# chess.net
KiCad netlist of a schematic drawn in EAGLE
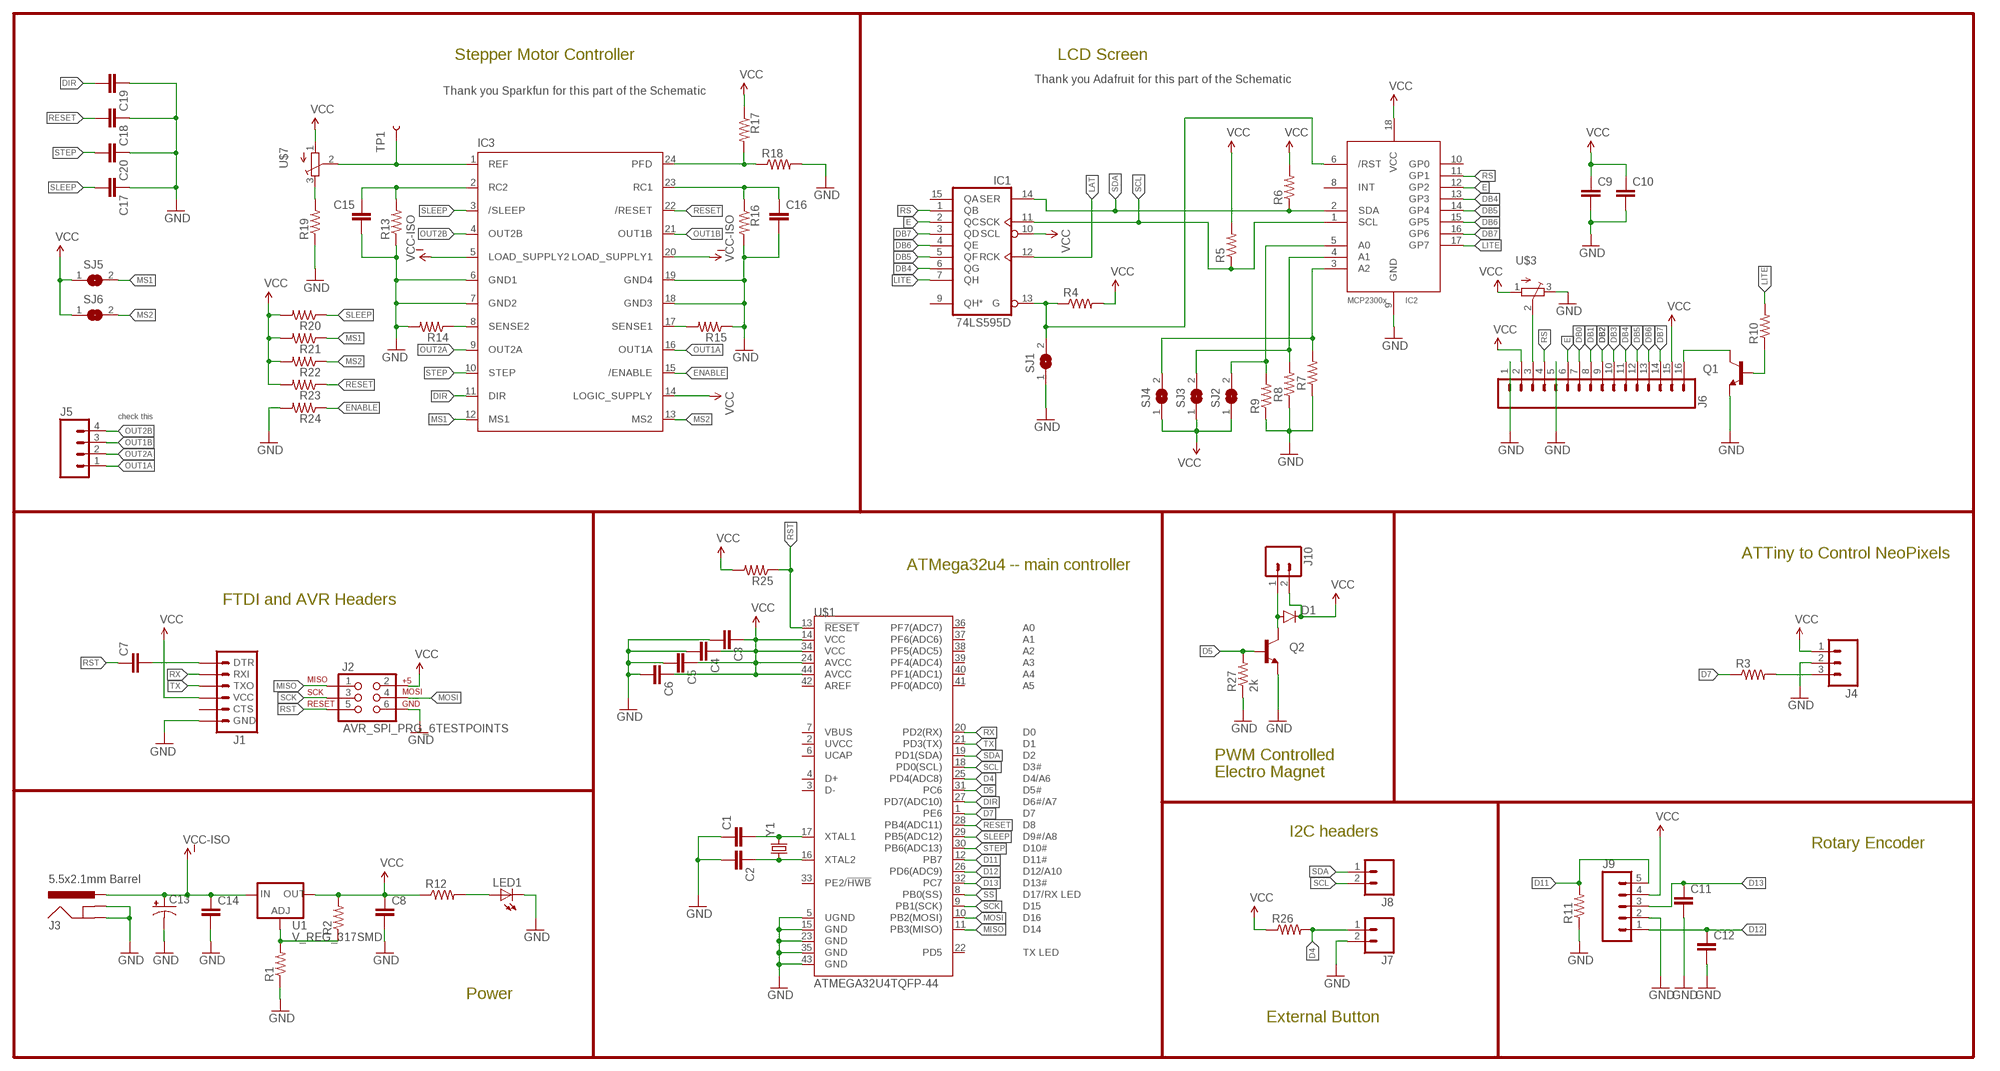
[diagram p0: schematic, sheet 1]

(export (version "E")
  (design (tool "Eeschema 10.0.6"))
  (components
    (comp (ref "C1")
      (value "CAP0603-CAP")
      (footprint "eagle-import:0603-CAP")
      (libsource (lib "eagle-import") (part "CAP0603-CAP"))
    )
    (comp (ref "C2")
      (value "CAP0603-CAP")
      (footprint "eagle-import:0603-CAP")
      (libsource (lib "eagle-import") (part "CAP0603-CAP"))
    )
    (comp (ref "C3")
      (value "CAP0603-CAP")
      (footprint "eagle-import:0603-CAP")
      (libsource (lib "eagle-import") (part "CAP0603-CAP"))
    )
    (comp (ref "C4")
      (value "CAP0603-CAP")
      (footprint "eagle-import:0603-CAP")
      (libsource (lib "eagle-import") (part "CAP0603-CAP"))
    )
    (comp (ref "C5")
      (value "CAP0603-CAP")
      (footprint "eagle-import:0603-CAP")
      (libsource (lib "eagle-import") (part "CAP0603-CAP"))
    )
    (comp (ref "C6")
      (value "CAP0603-CAP")
      (footprint "eagle-import:0603-CAP")
      (libsource (lib "eagle-import") (part "CAP0603-CAP"))
    )
    (comp (ref "C7")
      (value "CAP0603-CAP")
      (footprint "eagle-import:0603-CAP")
      (libsource (lib "eagle-import") (part "CAP0603-CAP"))
    )
    (comp (ref "C8")
      (value "CAP0603-CAP")
      (footprint "eagle-import:0603-CAP")
      (libsource (lib "eagle-import") (part "CAP0603-CAP"))
    )
    (comp (ref "C9")
      (value "CAP0603-CAP")
      (footprint "eagle-import:0603-CAP")
      (libsource (lib "eagle-import") (part "CAP0603-CAP"))
    )
    (comp (ref "C10")
      (value "CAP0603-CAP")
      (footprint "eagle-import:0603-CAP")
      (libsource (lib "eagle-import") (part "CAP0603-CAP"))
    )
    (comp (ref "C11")
      (value "CAP0603-CAP")
      (footprint "eagle-import:0603-CAP")
      (libsource (lib "eagle-import") (part "CAP0603-CAP"))
    )
    (comp (ref "C12")
      (value "CAP0603-CAP")
      (footprint "eagle-import:0603-CAP")
      (libsource (lib "eagle-import") (part "CAP0603-CAP"))
    )
    (comp (ref "C13")
      (value "CAP_POL6032")
      (footprint "eagle-import:EIA6032")
      (libsource (lib "eagle-import") (part "CAP_POL6032"))
    )
    (comp (ref "C14")
      (value "CAP0603-CAP")
      (footprint "eagle-import:0603-CAP")
      (libsource (lib "eagle-import") (part "CAP0603-CAP"))
    )
    (comp (ref "C15")
      (value "CAP0603-CAP")
      (footprint "eagle-import:0603-CAP")
      (libsource (lib "eagle-import") (part "CAP0603-CAP"))
    )
    (comp (ref "C16")
      (value "CAP0603-CAP")
      (footprint "eagle-import:0603-CAP")
      (libsource (lib "eagle-import") (part "CAP0603-CAP"))
    )
    (comp (ref "C17")
      (value "CAP0603-CAP")
      (footprint "eagle-import:0603-CAP")
      (libsource (lib "eagle-import") (part "CAP0603-CAP"))
    )
    (comp (ref "C18")
      (value "CAP0603-CAP")
      (footprint "eagle-import:0603-CAP")
      (libsource (lib "eagle-import") (part "CAP0603-CAP"))
    )
    (comp (ref "C19")
      (value "CAP0603-CAP")
      (footprint "eagle-import:0603-CAP")
      (libsource (lib "eagle-import") (part "CAP0603-CAP"))
    )
    (comp (ref "C20")
      (value "CAP0603-CAP")
      (footprint "eagle-import:0603-CAP")
      (libsource (lib "eagle-import") (part "CAP0603-CAP"))
    )
    (comp (ref "D1")
      (value "DIODEBAS16")
      (footprint "eagle-import:SOD-323")
      (libsource (lib "eagle-import") (part "DIODEBAS16"))
    )
    (comp (ref "IC1")
      (value "74LS595D")
      (footprint "eagle-import:SO16")
      (libsource (lib "eagle-import") (part "74595DLS"))
    )
    (comp (ref "IC2")
      (value "MCP2300X/SO")
      (footprint "eagle-import:SO18W")
      (libsource (lib "eagle-import") (part "MCP2300X/SO"))
    )
    (comp (ref "IC3")
      (value "A3967SLB")
      (footprint "eagle-import:SO24W")
      (libsource (lib "eagle-import") (part "A3967SLB"))
    )
    (comp (ref "J1")
      (value "ARDUINO_SERIAL_PROGRAMPTH")
      (footprint "eagle-import:1X06")
      (libsource (lib "eagle-import") (part "ARDUINO_SERIAL_PROGRAMPTH"))
    )
    (comp (ref "J2")
      (value "AVR_SPI_PRG_6TESTPOINTS")
      (footprint "eagle-import:2X3_TEST_POINTS")
      (libsource (lib "eagle-import") (part "AVR_SPI_PRG_6TESTPOINTS"))
    )
    (comp (ref "J3")
      (value "5.5x2.1mm Barrel")
      (footprint "eagle-import:POWER_JACK_SMD")
      (libsource (lib "eagle-import") (part "POWER_JACKSMD"))
    )
    (comp (ref "J4")
      (value "M03PTH")
      (footprint "eagle-import:1X03")
      (libsource (lib "eagle-import") (part "M03PTH"))
    )
    (comp (ref "J5")
      (value "M04PTH")
      (footprint "eagle-import:1X04")
      (libsource (lib "eagle-import") (part "M04PTH"))
    )
    (comp (ref "J6")
      (value "M16PTH")
      (footprint "eagle-import:1X16")
      (libsource (lib "eagle-import") (part "M16PTH"))
    )
    (comp (ref "J7")
      (value "M02PTH")
      (footprint "eagle-import:1X02")
      (libsource (lib "eagle-import") (part "M02PTH"))
    )
    (comp (ref "J8")
      (value "M02PTH")
      (footprint "eagle-import:1X02")
      (libsource (lib "eagle-import") (part "M02PTH"))
    )
    (comp (ref "J9")
      (value "M05PTH")
      (footprint "eagle-import:1X05")
      (libsource (lib "eagle-import") (part "M05PTH"))
    )
    (comp (ref "J10")
      (value "M02PTH")
      (footprint "eagle-import:1X02")
      (libsource (lib "eagle-import") (part "M02PTH"))
    )
    (comp (ref "LED1")
      (value "LED1206")
      (footprint "eagle-import:LED-1206")
      (libsource (lib "eagle-import") (part "LED1206"))
    )
    (comp (ref "Q1")
      (value "TRANSISTOR_NPNMMBT2222A")
      (footprint "eagle-import:SOT23-3")
      (libsource (lib "eagle-import") (part "TRANSISTOR_NPNMMBT2222A"))
    )
    (comp (ref "Q2")
      (value "TRANSISTOR_NPNTO-92-AMMO")
      (footprint "eagle-import:TO-92-AMMO")
      (libsource (lib "eagle-import") (part "TRANSISTOR_NPNTO-92-AMMO"))
    )
    (comp (ref "R1")
      (value "RESISTOR0603-RES")
      (footprint "eagle-import:0603-RES")
      (libsource (lib "eagle-import") (part "RESISTOR0603-RES"))
    )
    (comp (ref "R2")
      (value "RESISTOR0603-RES")
      (footprint "eagle-import:0603-RES")
      (libsource (lib "eagle-import") (part "RESISTOR0603-RES"))
    )
    (comp (ref "R3")
      (value "RESISTOR0603-RES")
      (footprint "eagle-import:0603-RES")
      (libsource (lib "eagle-import") (part "RESISTOR0603-RES"))
    )
    (comp (ref "R4")
      (value "RESISTOR0603-RES")
      (footprint "eagle-import:0603-RES")
      (libsource (lib "eagle-import") (part "RESISTOR0603-RES"))
    )
    (comp (ref "R5")
      (value "RESISTOR0603-RES")
      (footprint "eagle-import:0603-RES")
      (libsource (lib "eagle-import") (part "RESISTOR0603-RES"))
    )
    (comp (ref "R6")
      (value "RESISTOR0603-RES")
      (footprint "eagle-import:0603-RES")
      (libsource (lib "eagle-import") (part "RESISTOR0603-RES"))
    )
    (comp (ref "R7")
      (value "RESISTOR0603-RES")
      (footprint "eagle-import:0603-RES")
      (libsource (lib "eagle-import") (part "RESISTOR0603-RES"))
    )
    (comp (ref "R8")
      (value "RESISTOR0603-RES")
      (footprint "eagle-import:0603-RES")
      (libsource (lib "eagle-import") (part "RESISTOR0603-RES"))
    )
    (comp (ref "R9")
      (value "RESISTOR0603-RES")
      (footprint "eagle-import:0603-RES")
      (libsource (lib "eagle-import") (part "RESISTOR0603-RES"))
    )
    (comp (ref "R10")
      (value "RESISTOR0603-RES")
      (footprint "eagle-import:0603-RES")
      (libsource (lib "eagle-import") (part "RESISTOR0603-RES"))
    )
    (comp (ref "R11")
      (value "RESISTOR0603-RES")
      (footprint "eagle-import:0603-RES")
      (libsource (lib "eagle-import") (part "RESISTOR0603-RES"))
    )
    (comp (ref "R12")
      (value "RESISTOR0603-RES")
      (footprint "eagle-import:0603-RES")
      (libsource (lib "eagle-import") (part "RESISTOR0603-RES"))
    )
    (comp (ref "R13")
      (value "RESISTOR0603-RES")
      (footprint "eagle-import:0603-RES")
      (libsource (lib "eagle-import") (part "RESISTOR0603-RES"))
    )
    (comp (ref "R14")
      (value "RESISTOR0603-RES")
      (footprint "eagle-import:0603-RES")
      (libsource (lib "eagle-import") (part "RESISTOR0603-RES"))
    )
    (comp (ref "R15")
      (value "RESISTOR0603-RES")
      (footprint "eagle-import:0603-RES")
      (libsource (lib "eagle-import") (part "RESISTOR0603-RES"))
    )
    (comp (ref "R16")
      (value "RESISTOR0603-RES")
      (footprint "eagle-import:0603-RES")
      (libsource (lib "eagle-import") (part "RESISTOR0603-RES"))
    )
    (comp (ref "R17")
      (value "RESISTOR0603-RES")
      (footprint "eagle-import:0603-RES")
      (libsource (lib "eagle-import") (part "RESISTOR0603-RES"))
    )
    (comp (ref "R18")
      (value "RESISTOR0603-RES")
      (footprint "eagle-import:0603-RES")
      (libsource (lib "eagle-import") (part "RESISTOR0603-RES"))
    )
    (comp (ref "R19")
      (value "RESISTOR0603-RES")
      (footprint "eagle-import:0603-RES")
      (libsource (lib "eagle-import") (part "RESISTOR0603-RES"))
    )
    (comp (ref "R20")
      (value "RESISTOR0603-RES")
      (footprint "eagle-import:0603-RES")
      (libsource (lib "eagle-import") (part "RESISTOR0603-RES"))
    )
    (comp (ref "R21")
      (value "RESISTOR0603-RES")
      (footprint "eagle-import:0603-RES")
      (libsource (lib "eagle-import") (part "RESISTOR0603-RES"))
    )
    (comp (ref "R22")
      (value "RESISTOR0603-RES")
      (footprint "eagle-import:0603-RES")
      (libsource (lib "eagle-import") (part "RESISTOR0603-RES"))
    )
    (comp (ref "R23")
      (value "RESISTOR0603-RES")
      (footprint "eagle-import:0603-RES")
      (libsource (lib "eagle-import") (part "RESISTOR0603-RES"))
    )
    (comp (ref "R24")
      (value "RESISTOR0603-RES")
      (footprint "eagle-import:0603-RES")
      (libsource (lib "eagle-import") (part "RESISTOR0603-RES"))
    )
    (comp (ref "R25")
      (value "RESISTOR0603-RES")
      (footprint "eagle-import:0603-RES")
      (libsource (lib "eagle-import") (part "RESISTOR0603-RES"))
    )
    (comp (ref "R26")
      (value "RESISTOR0603-RES")
      (footprint "eagle-import:0603-RES")
      (libsource (lib "eagle-import") (part "RESISTOR0603-RES"))
    )
    (comp (ref "R27")
      (value "2k")
      (footprint "eagle-import:0603-RES")
      (libsource (lib "eagle-import") (part "RESISTOR0603-RES"))
    )
    (comp (ref "SJ1") (value "SJ") (footprint "eagle-import:SJ") (libsource (lib "eagle-import") (part "SJ")))
    (comp (ref "SJ2") (value "SJ") (footprint "eagle-import:SJ") (libsource (lib "eagle-import") (part "SJ")))
    (comp (ref "SJ3") (value "SJ") (footprint "eagle-import:SJ") (libsource (lib "eagle-import") (part "SJ")))
    (comp (ref "SJ4") (value "SJ") (footprint "eagle-import:SJ") (libsource (lib "eagle-import") (part "SJ")))
    (comp (ref "SJ5") (value "SJ") (footprint "eagle-import:SJ") (libsource (lib "eagle-import") (part "SJ")))
    (comp (ref "SJ6") (value "SJ") (footprint "eagle-import:SJ") (libsource (lib "eagle-import") (part "SJ")))
    (comp (ref "TP1")
      (value "TEST-POINT3X5")
      (footprint "eagle-import:PAD.03X.05")
      (libsource (lib "eagle-import") (part "TEST-POINT3X5"))
    )
    (comp (ref "U$1")
      (value "ATMEGA32U4TQFP-44")
      (footprint "eagle-import:TQFP44")
      (libsource (lib "eagle-import") (part "ATMEGA32U4TQFP-44"))
    )
    (comp (ref "U$3")
      (value "TRIMPOTTC33X")
      (footprint "eagle-import:TC33X")
      (libsource (lib "eagle-import") (part "TRIMPOTTC33X"))
    )
    (comp (ref "U$7")
      (value "TRIMPOTTC33X")
      (footprint "eagle-import:TC33X")
      (libsource (lib "eagle-import") (part "TRIMPOTTC33X"))
    )
    (comp (ref "U1")
      (value "V_REG_317SMD")
      (footprint "eagle-import:SOT223")
      (libsource (lib "eagle-import") (part "V_REG_317SMD"))
    )
    (comp (ref "Y1")
      (value "CRYSTALCRYSTAL-SMD-5X3-12MHZ")
      (footprint "eagle-import:CRYSTAL-SMD-5X3")
      (libsource (lib "eagle-import") (part "CRYSTALCRYSTAL-SMD-5X3-12MHZ"))
    )
  )
  (nets
    (net (code "1") (name "D4") (class "Default")
      (node (ref "J7") (pin "1") (pinfunction "1_1") (pintype "passive"))
      (node (ref "R26") (pin "2") (pinfunction "2_2") (pintype "passive"))
      (node (ref "U$1") (pin "25") (pinfunction "PD4(ADC8)_25") (pintype "bidirectional"))
    )
    (net (code "2") (name "D5") (class "Default")
      (node (ref "Q2") (pin "2") (pinfunction "B_2") (pintype "passive"))
      (node (ref "R27") (pin "2") (pinfunction "2_2") (pintype "passive"))
      (node (ref "U$1") (pin "31") (pinfunction "PC6_31") (pintype "bidirectional"))
    )
    (net (code "3") (name "D7") (class "Default")
      (node (ref "R3") (pin "1") (pinfunction "1_1") (pintype "passive"))
      (node (ref "U$1") (pin "1") (pinfunction "PE6_1") (pintype "bidirectional"))
    )
    (net (code "4") (name "D11") (class "Default")
      (node (ref "J9") (pin "5") (pinfunction "5_5") (pintype "passive"))
      (node (ref "R11") (pin "2") (pinfunction "2_2") (pintype "passive"))
      (node (ref "U$1") (pin "12") (pinfunction "PB7_12") (pintype "bidirectional"))
    )
    (net (code "5") (name "D12") (class "Default")
      (node (ref "C12") (pin "1") (pinfunction "1_1") (pintype "passive"))
      (node (ref "J9") (pin "1") (pinfunction "1_1") (pintype "passive"))
      (node (ref "U$1") (pin "26") (pinfunction "PD6(ADC9)_26") (pintype "bidirectional"))
    )
    (net (code "6") (name "D13") (class "Default")
      (node (ref "C11") (pin "1") (pinfunction "1_1") (pintype "passive"))
      (node (ref "J9") (pin "3") (pinfunction "3_3") (pintype "passive"))
      (node (ref "U$1") (pin "32") (pinfunction "PC7_32") (pintype "bidirectional"))
    )
    (net (code "7") (name "DB0") (class "Default")
      (node (ref "J6") (pin "7") (pinfunction "7_7") (pintype "passive"))
    )
    (net (code "8") (name "DB1") (class "Default")
      (node (ref "J6") (pin "8") (pinfunction "8_8") (pintype "passive"))
    )
    (net (code "9") (name "DB2") (class "Default")
      (node (ref "J6") (pin "9") (pinfunction "9_9") (pintype "passive"))
    )
    (net (code "10") (name "DB3") (class "Default")
      (node (ref "J6") (pin "10") (pinfunction "10_10") (pintype "passive"))
    )
    (net (code "11") (name "DB4") (class "Default")
      (node (ref "IC1") (pin "6") (pinfunction "QG_6") (pintype "tri_state"))
      (node (ref "IC2") (pin "13") (pinfunction "GP3_13") (pintype "bidirectional"))
      (node (ref "J6") (pin "11") (pinfunction "11_11") (pintype "passive"))
    )
    (net (code "12") (name "DB5") (class "Default")
      (node (ref "IC1") (pin "5") (pinfunction "QF_5") (pintype "tri_state"))
      (node (ref "IC2") (pin "14") (pinfunction "GP4_14") (pintype "bidirectional"))
      (node (ref "J6") (pin "12") (pinfunction "12_12") (pintype "passive"))
    )
    (net (code "13") (name "DB6") (class "Default")
      (node (ref "IC1") (pin "4") (pinfunction "QE_4") (pintype "tri_state"))
      (node (ref "IC2") (pin "15") (pinfunction "GP5_15") (pintype "bidirectional"))
      (node (ref "J6") (pin "13") (pinfunction "13_13") (pintype "passive"))
    )
    (net (code "14") (name "DB7") (class "Default")
      (node (ref "IC1") (pin "3") (pinfunction "QD_3") (pintype "tri_state"))
      (node (ref "IC2") (pin "16") (pinfunction "GP6_16") (pintype "bidirectional"))
      (node (ref "J6") (pin "14") (pinfunction "14_14") (pintype "passive"))
    )
    (net (code "15") (name "DIR") (class "Default")
      (node (ref "C19") (pin "2") (pinfunction "2_2") (pintype "passive"))
      (node (ref "IC3") (pin "11") (pinfunction "DIR_11") (pintype "power_in"))
      (node (ref "U$1") (pin "27") (pinfunction "PD7(ADC10)_27") (pintype "bidirectional"))
    )
    (net (code "16") (name "E") (class "Default")
      (node (ref "IC1") (pin "2") (pinfunction "QC_2") (pintype "tri_state"))
      (node (ref "IC2") (pin "12") (pinfunction "GP2_12") (pintype "bidirectional"))
      (node (ref "J6") (pin "6") (pinfunction "6_6") (pintype "passive"))
    )
    (net (code "17") (name "ENABLE") (class "Default")
      (node (ref "IC3") (pin "15") (pinfunction "/ENABLE_15") (pintype "tri_state"))
      (node (ref "R24") (pin "1") (pinfunction "1_1") (pintype "passive"))
    )
    (net (code "18") (name "GND") (class "Default")
      (node (ref "C1") (pin "1") (pinfunction "1_1") (pintype "passive"))
      (node (ref "C10") (pin "2") (pinfunction "2_2") (pintype "passive"))
      (node (ref "C11") (pin "2") (pinfunction "2_2") (pintype "passive"))
      (node (ref "C12") (pin "2") (pinfunction "2_2") (pintype "passive"))
      (node (ref "C13") (pin "P$2") (pinfunction "-_P$2") (pintype "passive"))
      (node (ref "C14") (pin "2") (pinfunction "2_2") (pintype "passive"))
      (node (ref "C15") (pin "2") (pinfunction "2_2") (pintype "passive"))
      (node (ref "C16") (pin "2") (pinfunction "2_2") (pintype "passive"))
      (node (ref "C17") (pin "1") (pinfunction "1_1") (pintype "passive"))
      (node (ref "C18") (pin "1") (pinfunction "1_1") (pintype "passive"))
      (node (ref "C19") (pin "1") (pinfunction "1_1") (pintype "passive"))
      (node (ref "C2") (pin "2") (pinfunction "2_2") (pintype "passive"))
      (node (ref "C20") (pin "1") (pinfunction "1_1") (pintype "passive"))
      (node (ref "C3") (pin "2") (pinfunction "2_2") (pintype "passive"))
      (node (ref "C4") (pin "2") (pinfunction "2_2") (pintype "passive"))
      (node (ref "C5") (pin "2") (pinfunction "2_2") (pintype "passive"))
      (node (ref "C6") (pin "2") (pinfunction "2_2") (pintype "passive"))
      (node (ref "C8") (pin "2") (pinfunction "2_2") (pintype "passive"))
      (node (ref "C9") (pin "2") (pinfunction "2_2") (pintype "passive"))
      (node (ref "IC2") (pin "9") (pinfunction "GND_9") (pintype "power_in"))
      (node (ref "IC3") (pin "18") (pinfunction "GND3_18") (pintype "tri_state"))
      (node (ref "IC3") (pin "19") (pinfunction "GND4_19") (pintype "tri_state"))
      (node (ref "IC3") (pin "6") (pinfunction "GND1_6") (pintype "passive"))
      (node (ref "IC3") (pin "7") (pinfunction "GND2_7") (pintype "output"))
      (node (ref "J1") (pin "6") (pinfunction "GND_6") (pintype "passive"))
      (node (ref "J2") (pin "6") (pinfunction "6_6") (pintype "passive"))
      (node (ref "J3") (pin "GND") (pinfunction "GNDBREAK_GND") (pintype "bidirectional"))
      (node (ref "J3") (pin "P$4") (pinfunction "GND_P$4") (pintype "bidirectional"))
      (node (ref "J4") (pin "2") (pinfunction "2_2") (pintype "passive"))
      (node (ref "J6") (pin "1") (pinfunction "1_1") (pintype "passive"))
      (node (ref "J6") (pin "5") (pinfunction "5_5") (pintype "passive"))
      (node (ref "J7") (pin "2") (pinfunction "2_2") (pintype "passive"))
      (node (ref "J9") (pin "2") (pinfunction "2_2") (pintype "passive"))
      (node (ref "LED1") (pin "C") (pinfunction "C_C") (pintype "passive"))
      (node (ref "Q1") (pin "2") (pinfunction "E_2") (pintype "passive"))
      (node (ref "Q2") (pin "1") (pinfunction "E_1") (pintype "passive"))
      (node (ref "R1") (pin "1") (pinfunction "1_1") (pintype "passive"))
      (node (ref "R11") (pin "1") (pinfunction "1_1") (pintype "passive"))
      (node (ref "R13") (pin "1") (pinfunction "1_1") (pintype "passive"))
      (node (ref "R14") (pin "2") (pinfunction "2_2") (pintype "passive"))
      (node (ref "R15") (pin "1") (pinfunction "1_1") (pintype "passive"))
      (node (ref "R16") (pin "2") (pinfunction "2_2") (pintype "passive"))
      (node (ref "R18") (pin "2") (pinfunction "2_2") (pintype "passive"))
      (node (ref "R19") (pin "1") (pinfunction "1_1") (pintype "passive"))
      (node (ref "R24") (pin "2") (pinfunction "2_2") (pintype "passive"))
      (node (ref "R27") (pin "1") (pinfunction "1_1") (pintype "passive"))
      (node (ref "R7") (pin "1") (pinfunction "1_1") (pintype "passive"))
      (node (ref "R8") (pin "1") (pinfunction "1_1") (pintype "passive"))
      (node (ref "R9") (pin "1") (pinfunction "1_1") (pintype "passive"))
      (node (ref "SJ1") (pin "1") (pinfunction "1_1") (pintype "passive"))
      (node (ref "U$1") (pin "15") (pinfunction "GND_15") (pintype "bidirectional"))
      (node (ref "U$1") (pin "23") (pinfunction "GND_23") (pintype "bidirectional"))
      (node (ref "U$1") (pin "35") (pinfunction "GND_35") (pintype "bidirectional"))
      (node (ref "U$1") (pin "43") (pinfunction "GND_43") (pintype "bidirectional"))
      (node (ref "U$1") (pin "5") (pinfunction "UGND_5") (pintype "bidirectional"))
      (node (ref "U$3") (pin "3") (pinfunction "E_3") (pintype "passive"))
    )
    (net (code "19") (name "LAT") (class "Default")
      (node (ref "IC1") (pin "12") (pinfunction "RCK_12") (pintype "input"))
    )
    (net (code "20") (name "LITE") (class "Default")
      (node (ref "IC1") (pin "7") (pinfunction "QH_7") (pintype "tri_state"))
      (node (ref "IC2") (pin "17") (pinfunction "GP7_17") (pintype "bidirectional"))
      (node (ref "R10") (pin "2") (pinfunction "2_2") (pintype "passive"))
    )
    (net (code "21") (name "MISO") (class "Default")
      (node (ref "J2") (pin "1") (pinfunction "1_1") (pintype "passive"))
      (node (ref "U$1") (pin "11") (pinfunction "PB3(MISO)_11") (pintype "bidirectional"))
    )
    (net (code "22") (name "MOSI") (class "Default")
      (node (ref "J2") (pin "4") (pinfunction "4_4") (pintype "passive"))
      (node (ref "U$1") (pin "10") (pinfunction "PB2(MOSI)_10") (pintype "bidirectional"))
    )
    (net (code "23") (name "MS1") (class "Default")
      (node (ref "IC3") (pin "12") (pinfunction "MS1_12") (pintype "output"))
      (node (ref "R21") (pin "1") (pinfunction "1_1") (pintype "passive"))
      (node (ref "SJ5") (pin "2") (pinfunction "2_2") (pintype "passive"))
    )
    (net (code "24") (name "MS2") (class "Default")
      (node (ref "IC3") (pin "13") (pinfunction "MS2_13") (pintype "tri_state"))
      (node (ref "R22") (pin "1") (pinfunction "1_1") (pintype "passive"))
      (node (ref "SJ6") (pin "2") (pinfunction "2_2") (pintype "passive"))
    )
    (net (code "25") (name "Net-(IC1A-G)") (class "Default")
      (node (ref "IC1") (pin "13") (pinfunction "G_13") (pintype "input"))
      (node (ref "IC2") (pin "6") (pinfunction "/RST_6") (pintype "input"))
      (node (ref "R4") (pin "1") (pinfunction "1_1") (pintype "passive"))
      (node (ref "SJ1") (pin "2") (pinfunction "2_2") (pintype "passive"))
    )
    (net (code "26") (name "Net-(IC2-A0)") (class "Default")
      (node (ref "IC2") (pin "5") (pinfunction "A0_5") (pintype "input"))
      (node (ref "R9") (pin "2") (pinfunction "2_2") (pintype "passive"))
      (node (ref "SJ2") (pin "2") (pinfunction "2_2") (pintype "passive"))
    )
    (net (code "27") (name "Net-(IC2-A1)") (class "Default")
      (node (ref "IC2") (pin "4") (pinfunction "A1_4") (pintype "input"))
      (node (ref "R8") (pin "2") (pinfunction "2_2") (pintype "passive"))
      (node (ref "SJ3") (pin "2") (pinfunction "2_2") (pintype "passive"))
    )
    (net (code "28") (name "Net-(IC2-A2)") (class "Default")
      (node (ref "IC2") (pin "3") (pinfunction "A2_3") (pintype "input"))
      (node (ref "R7") (pin "2") (pinfunction "2_2") (pintype "passive"))
      (node (ref "SJ4") (pin "2") (pinfunction "2_2") (pintype "passive"))
    )
    (net (code "29") (name "Net-(IC3-PFD)") (class "Default")
      (node (ref "IC3") (pin "24") (pinfunction "PFD_24") (pintype "tri_state"))
      (node (ref "R17") (pin "2") (pinfunction "2_2") (pintype "passive"))
      (node (ref "R18") (pin "1") (pinfunction "1_1") (pintype "passive"))
    )
    (net (code "30") (name "Net-(IC3-RC1)") (class "Default")
      (node (ref "C16") (pin "1") (pinfunction "1_1") (pintype "passive"))
      (node (ref "IC3") (pin "23") (pinfunction "RC1_23") (pintype "tri_state"))
      (node (ref "R16") (pin "1") (pinfunction "1_1") (pintype "passive"))
    )
    (net (code "31") (name "Net-(IC3-RC2)") (class "Default")
      (node (ref "C15") (pin "1") (pinfunction "1_1") (pintype "passive"))
      (node (ref "IC3") (pin "2") (pinfunction "RC2_2") (pintype "input"))
      (node (ref "R13") (pin "2") (pinfunction "2_2") (pintype "passive"))
    )
    (net (code "32") (name "Net-(IC3-REF)") (class "Default")
      (node (ref "IC3") (pin "1") (pinfunction "REF_1") (pintype "power_in"))
      (node (ref "TP1") (pin "P$1") (pinfunction "1_P$1") (pintype "bidirectional"))
      (node (ref "U$7") (pin "2") (pinfunction "S_2") (pintype "passive"))
    )
    (net (code "33") (name "Net-(IC3-SENSE1)") (class "Default")
      (node (ref "IC3") (pin "17") (pinfunction "SENSE1_17") (pintype "tri_state"))
      (node (ref "R15") (pin "2") (pinfunction "2_2") (pintype "passive"))
    )
    (net (code "34") (name "Net-(IC3-SENSE2)") (class "Default")
      (node (ref "IC3") (pin "8") (pinfunction "SENSE2_8") (pintype "input"))
      (node (ref "R14") (pin "1") (pinfunction "1_1") (pintype "passive"))
    )
    (net (code "35") (name "Net-(J1-DTR)") (class "Default")
      (node (ref "C7") (pin "2") (pinfunction "2_2") (pintype "passive"))
      (node (ref "J1") (pin "1") (pinfunction "DTR_1") (pintype "passive"))
    )
    (net (code "36") (name "Net-(J4-Pad3)") (class "Default")
      (node (ref "J4") (pin "3") (pinfunction "3_3") (pintype "passive"))
      (node (ref "R3") (pin "2") (pinfunction "2_2") (pintype "passive"))
    )
    (net (code "37") (name "Net-(LED1-PadA)") (class "Default")
      (node (ref "LED1") (pin "A") (pinfunction "A_A") (pintype "passive"))
      (node (ref "R12") (pin "2") (pinfunction "2_2") (pintype "passive"))
    )
    (net (code "38") (name "Net-(Q1-B)") (class "Default")
      (node (ref "Q1") (pin "1") (pinfunction "B_1") (pintype "passive"))
      (node (ref "R10") (pin "1") (pinfunction "1_1") (pintype "passive"))
    )
    (net (code "39") (name "Net-(Q1-C)") (class "Default")
      (node (ref "J6") (pin "16") (pinfunction "16_16") (pintype "passive"))
      (node (ref "Q1") (pin "3") (pinfunction "C_3") (pintype "passive"))
    )
    (net (code "40") (name "Net-(Q2-C)") (class "Default")
      (node (ref "D1") (pin "A") (pinfunction "A_A") (pintype "passive"))
      (node (ref "J10") (pin "1") (pinfunction "1_1") (pintype "passive"))
      (node (ref "Q2") (pin "3") (pinfunction "C_3") (pintype "passive"))
    )
    (net (code "41") (name "Net-(U$1-XTAL1)") (class "Default")
      (node (ref "C1") (pin "2") (pinfunction "2_2") (pintype "passive"))
      (node (ref "U$1") (pin "17") (pinfunction "XTAL1_17") (pintype "bidirectional"))
      (node (ref "Y1") (pin "3") (pinfunction "2_3") (pintype "passive"))
    )
    (net (code "42") (name "Net-(U$1-XTAL2)") (class "Default")
      (node (ref "C2") (pin "1") (pinfunction "1_1") (pintype "passive"))
      (node (ref "U$1") (pin "16") (pinfunction "XTAL2_16") (pintype "bidirectional"))
      (node (ref "Y1") (pin "1") (pinfunction "1_1") (pintype "passive"))
    )
    (net (code "43") (name "Net-(U$3-S)") (class "Default")
      (node (ref "J6") (pin "3") (pinfunction "3_3") (pintype "passive"))
      (node (ref "U$3") (pin "2") (pinfunction "S_2") (pintype "passive"))
    )
    (net (code "44") (name "Net-(U$7-E)") (class "Default")
      (node (ref "R19") (pin "2") (pinfunction "2_2") (pintype "passive"))
      (node (ref "U$7") (pin "3") (pinfunction "E_3") (pintype "passive"))
    )
    (net (code "45") (name "Net-(U1-ADJ)") (class "Default")
      (node (ref "R1") (pin "2") (pinfunction "2_2") (pintype "passive"))
      (node (ref "R2") (pin "1") (pinfunction "1_1") (pintype "passive"))
      (node (ref "U1") (pin "1") (pinfunction "ADJ_1") (pintype "input"))
    )
    (net (code "46") (name "OUT1A") (class "Default")
      (node (ref "IC3") (pin "16") (pinfunction "OUT1A_16") (pintype "tri_state"))
      (node (ref "J5") (pin "1") (pinfunction "1_1") (pintype "passive"))
    )
    (net (code "47") (name "OUT1B") (class "Default")
      (node (ref "IC3") (pin "21") (pinfunction "OUT1B_21") (pintype "tri_state"))
      (node (ref "J5") (pin "3") (pinfunction "3_3") (pintype "passive"))
    )
    (net (code "48") (name "OUT2A") (class "Default")
      (node (ref "IC3") (pin "9") (pinfunction "OUT2A_9") (pintype "power_in"))
      (node (ref "J5") (pin "2") (pinfunction "2_2") (pintype "passive"))
    )
    (net (code "49") (name "OUT2B") (class "Default")
      (node (ref "IC3") (pin "4") (pinfunction "OUT2B_4") (pintype "passive"))
      (node (ref "J5") (pin "4") (pinfunction "4_4") (pintype "passive"))
    )
    (net (code "50") (name "RESET") (class "Default")
      (node (ref "C18") (pin "2") (pinfunction "2_2") (pintype "passive"))
      (node (ref "IC3") (pin "22") (pinfunction "/RESET_22") (pintype "tri_state"))
      (node (ref "R23") (pin "1") (pinfunction "1_1") (pintype "passive"))
      (node (ref "U$1") (pin "28") (pinfunction "PB4(ADC11)_28") (pintype "bidirectional"))
    )
    (net (code "51") (name "RS") (class "Default")
      (node (ref "IC1") (pin "1") (pinfunction "QB_1") (pintype "tri_state"))
      (node (ref "IC2") (pin "11") (pinfunction "GP1_11") (pintype "bidirectional"))
      (node (ref "J6") (pin "4") (pinfunction "4_4") (pintype "passive"))
    )
    (net (code "52") (name "RST") (class "Default")
      (node (ref "C7") (pin "1") (pinfunction "1_1") (pintype "passive"))
      (node (ref "J2") (pin "5") (pinfunction "5_5") (pintype "passive"))
      (node (ref "R25") (pin "1") (pinfunction "1_1") (pintype "passive"))
      (node (ref "U$1") (pin "13") (pinfunction "~{RESET}_13") (pintype "bidirectional"))
    )
    (net (code "53") (name "RX") (class "Default")
      (node (ref "J1") (pin "2") (pinfunction "RXI_2") (pintype "passive"))
      (node (ref "U$1") (pin "20") (pinfunction "PD2(RX)_20") (pintype "bidirectional"))
    )
    (net (code "54") (name "SCK") (class "Default")
      (node (ref "J2") (pin "3") (pinfunction "3_3") (pintype "passive"))
      (node (ref "U$1") (pin "9") (pinfunction "PB1(SCK)_9") (pintype "bidirectional"))
    )
    (net (code "55") (name "SCL") (class "Default")
      (node (ref "IC1") (pin "11") (pinfunction "SCK_11") (pintype "input"))
      (node (ref "IC2") (pin "1") (pinfunction "SCL_1") (pintype "bidirectional"))
      (node (ref "J8") (pin "2") (pinfunction "2_2") (pintype "passive"))
      (node (ref "R5") (pin "1") (pinfunction "1_1") (pintype "passive"))
      (node (ref "U$1") (pin "18") (pinfunction "PD0(SCL)_18") (pintype "bidirectional"))
    )
    (net (code "56") (name "SDA") (class "Default")
      (node (ref "IC1") (pin "14") (pinfunction "SER_14") (pintype "input"))
      (node (ref "IC2") (pin "2") (pinfunction "SDA_2") (pintype "bidirectional"))
      (node (ref "J8") (pin "1") (pinfunction "1_1") (pintype "passive"))
      (node (ref "R6") (pin "1") (pinfunction "1_1") (pintype "passive"))
      (node (ref "U$1") (pin "19") (pinfunction "PD1(SDA)_19") (pintype "bidirectional"))
    )
    (net (code "57") (name "SLEEP") (class "Default")
      (node (ref "C17") (pin "2") (pinfunction "2_2") (pintype "passive"))
      (node (ref "IC3") (pin "3") (pinfunction "/SLEEP_3") (pintype "passive"))
      (node (ref "R20") (pin "1") (pinfunction "1_1") (pintype "passive"))
      (node (ref "U$1") (pin "29") (pinfunction "PB5(ADC12)_29") (pintype "bidirectional"))
    )
    (net (code "58") (name "SS") (class "Default")
      (node (ref "U$1") (pin "8") (pinfunction "PB0(SS)_8") (pintype "bidirectional"))
    )
    (net (code "59") (name "STEP") (class "Default")
      (node (ref "C20") (pin "2") (pinfunction "2_2") (pintype "passive"))
      (node (ref "IC3") (pin "10") (pinfunction "STEP_10") (pintype "power_in"))
      (node (ref "U$1") (pin "30") (pinfunction "PB6(ADC13)_30") (pintype "bidirectional"))
    )
    (net (code "60") (name "TX") (class "Default")
      (node (ref "J1") (pin "3") (pinfunction "TXO_3") (pintype "passive"))
      (node (ref "U$1") (pin "21") (pinfunction "PD3(TX)_21") (pintype "bidirectional"))
    )
    (net (code "61") (name "VCC") (class "Default")
      (node (ref "C10") (pin "1") (pinfunction "1_1") (pintype "passive"))
      (node (ref "C3") (pin "1") (pinfunction "1_1") (pintype "passive"))
      (node (ref "C4") (pin "1") (pinfunction "1_1") (pintype "passive"))
      (node (ref "C5") (pin "1") (pinfunction "1_1") (pintype "passive"))
      (node (ref "C6") (pin "1") (pinfunction "1_1") (pintype "passive"))
      (node (ref "C8") (pin "1") (pinfunction "1_1") (pintype "passive"))
      (node (ref "C9") (pin "1") (pinfunction "1_1") (pintype "passive"))
      (node (ref "D1") (pin "C") (pinfunction "C_C") (pintype "passive"))
      (node (ref "IC1") (pin "10") (pinfunction "SCL_10") (pintype "input"))
      (node (ref "IC2") (pin "18") (pinfunction "VCC_18") (pintype "power_in"))
      (node (ref "IC3") (pin "14") (pinfunction "LOGIC_SUPPLY_14") (pintype "tri_state"))
      (node (ref "J1") (pin "4") (pinfunction "VCC_4") (pintype "passive"))
      (node (ref "J10") (pin "2") (pinfunction "2_2") (pintype "passive"))
      (node (ref "J2") (pin "2") (pinfunction "2_2") (pintype "passive"))
      (node (ref "J4") (pin "1") (pinfunction "1_1") (pintype "passive"))
      (node (ref "J6") (pin "15") (pinfunction "15_15") (pintype "passive"))
      (node (ref "J6") (pin "2") (pinfunction "2_2") (pintype "passive"))
      (node (ref "J9") (pin "4") (pinfunction "4_4") (pintype "passive"))
      (node (ref "R12") (pin "1") (pinfunction "1_1") (pintype "passive"))
      (node (ref "R17") (pin "1") (pinfunction "1_1") (pintype "passive"))
      (node (ref "R2") (pin "2") (pinfunction "2_2") (pintype "passive"))
      (node (ref "R20") (pin "2") (pinfunction "2_2") (pintype "passive"))
      (node (ref "R21") (pin "2") (pinfunction "2_2") (pintype "passive"))
      (node (ref "R22") (pin "2") (pinfunction "2_2") (pintype "passive"))
      (node (ref "R23") (pin "2") (pinfunction "2_2") (pintype "passive"))
      (node (ref "R25") (pin "2") (pinfunction "2_2") (pintype "passive"))
      (node (ref "R26") (pin "1") (pinfunction "1_1") (pintype "passive"))
      (node (ref "R4") (pin "2") (pinfunction "2_2") (pintype "passive"))
      (node (ref "R5") (pin "2") (pinfunction "2_2") (pintype "passive"))
      (node (ref "R6") (pin "2") (pinfunction "2_2") (pintype "passive"))
      (node (ref "SJ2") (pin "1") (pinfunction "1_1") (pintype "passive"))
      (node (ref "SJ3") (pin "1") (pinfunction "1_1") (pintype "passive"))
      (node (ref "SJ4") (pin "1") (pinfunction "1_1") (pintype "passive"))
      (node (ref "SJ5") (pin "1") (pinfunction "1_1") (pintype "passive"))
      (node (ref "SJ6") (pin "1") (pinfunction "1_1") (pintype "passive"))
      (node (ref "U$1") (pin "14") (pinfunction "VCC_14") (pintype "bidirectional"))
      (node (ref "U$1") (pin "24") (pinfunction "AVCC_24") (pintype "bidirectional"))
      (node (ref "U$1") (pin "34") (pinfunction "VCC_34") (pintype "bidirectional"))
      (node (ref "U$1") (pin "44") (pinfunction "AVCC_44") (pintype "bidirectional"))
      (node (ref "U$3") (pin "1") (pinfunction "A_1") (pintype "passive"))
      (node (ref "U$7") (pin "1") (pinfunction "A_1") (pintype "passive"))
      (node (ref "U1") (pin "2") (pinfunction "OUT_2") (pintype "output"))
    )
    (net (code "62") (name "VCC-ISO") (class "Default")
      (node (ref "C13") (pin "P$1") (pinfunction "+_P$1") (pintype "passive"))
      (node (ref "C14") (pin "1") (pinfunction "1_1") (pintype "passive"))
      (node (ref "IC3") (pin "20") (pinfunction "LOAD_SUPPLY1_20") (pintype "tri_state"))
      (node (ref "IC3") (pin "5") (pinfunction "LOAD_SUPPLY2_5") (pintype "passive"))
      (node (ref "J3") (pin "VIN0") (pinfunction "PWR_VIN0") (pintype "bidirectional"))
      (node (ref "U1") (pin "3") (pinfunction "IN_3") (pintype "input"))
    )
    (net (code "63") (name "unconnected-(IC1A-QA-Pad15)") (class "Default")
      (node (ref "IC1") (pin "15") (pinfunction "QA_15") (pintype "tri_state"))
    )
    (net (code "64") (name "unconnected-(IC1A-QH*-Pad9)") (class "Default")
      (node (ref "IC1") (pin "9") (pinfunction "QH*_9") (pintype "tri_state"))
    )
    (net (code "65") (name "unconnected-(IC2-GP0-Pad10)") (class "Default")
      (node (ref "IC2") (pin "10") (pinfunction "GP0_10") (pintype "bidirectional"))
    )
    (net (code "66") (name "unconnected-(IC2-INT-Pad8)") (class "Default")
      (node (ref "IC2") (pin "8") (pinfunction "INT_8") (pintype "output"))
    )
    (net (code "67") (name "unconnected-(J1-CTS-Pad5)") (class "Default")
      (node (ref "J1") (pin "5") (pinfunction "CTS_5") (pintype "passive"))
    )
    (net (code "68") (name "unconnected-(U$1-AREF-Pad42)") (class "Default")
      (node (ref "U$1") (pin "42") (pinfunction "AREF_42") (pintype "bidirectional"))
    )
    (net (code "69") (name "unconnected-(U$1-D+-Pad4)") (class "Default")
      (node (ref "U$1") (pin "4") (pinfunction "D+_4") (pintype "bidirectional"))
    )
    (net (code "70") (name "unconnected-(U$1-D--Pad3)") (class "Default")
      (node (ref "U$1") (pin "3") (pinfunction "D-_3") (pintype "bidirectional"))
    )
    (net (code "71") (name "unconnected-(U$1-PD5-Pad22)") (class "Default")
      (node (ref "U$1") (pin "22") (pinfunction "PD5_22") (pintype "bidirectional"))
    )
    (net (code "72") (name "unconnected-(U$1-PE2{slash}~{HWB}-Pad33)") (class "Default")
      (node (ref "U$1") (pin "33") (pinfunction "PE2/~{HWB}_33") (pintype "bidirectional"))
    )
    (net (code "73") (name "unconnected-(U$1-PF0(ADC0)-Pad41)") (class "Default")
      (node (ref "U$1") (pin "41") (pinfunction "PF0(ADC0)_41") (pintype "bidirectional"))
    )
    (net (code "74") (name "unconnected-(U$1-PF1(ADC1)-Pad40)") (class "Default")
      (node (ref "U$1") (pin "40") (pinfunction "PF1(ADC1)_40") (pintype "bidirectional"))
    )
    (net (code "75") (name "unconnected-(U$1-PF4(ADC4)-Pad39)") (class "Default")
      (node (ref "U$1") (pin "39") (pinfunction "PF4(ADC4)_39") (pintype "bidirectional"))
    )
    (net (code "76") (name "unconnected-(U$1-PF5(ADC5)-Pad38)") (class "Default")
      (node (ref "U$1") (pin "38") (pinfunction "PF5(ADC5)_38") (pintype "bidirectional"))
    )
    (net (code "77") (name "unconnected-(U$1-PF6(ADC6)-Pad37)") (class "Default")
      (node (ref "U$1") (pin "37") (pinfunction "PF6(ADC6)_37") (pintype "bidirectional"))
    )
    (net (code "78") (name "unconnected-(U$1-PF7(ADC7)-Pad36)") (class "Default")
      (node (ref "U$1") (pin "36") (pinfunction "PF7(ADC7)_36") (pintype "bidirectional"))
    )
    (net (code "79") (name "unconnected-(U$1-UCAP-Pad6)") (class "Default")
      (node (ref "U$1") (pin "6") (pinfunction "UCAP_6") (pintype "bidirectional"))
    )
    (net (code "80") (name "unconnected-(U$1-UVCC-Pad2)") (class "Default")
      (node (ref "U$1") (pin "2") (pinfunction "UVCC_2") (pintype "bidirectional"))
    )
    (net (code "81") (name "unconnected-(U$1-VBUS-Pad7)") (class "Default")
      (node (ref "U$1") (pin "7") (pinfunction "VBUS_7") (pintype "bidirectional"))
    )
  )
)
